# LCDTFT_CTP_FPC6P_10_1INCH_ER-TPC101-1.net
KiCad netlist of a schematic drawn in Altium Designer
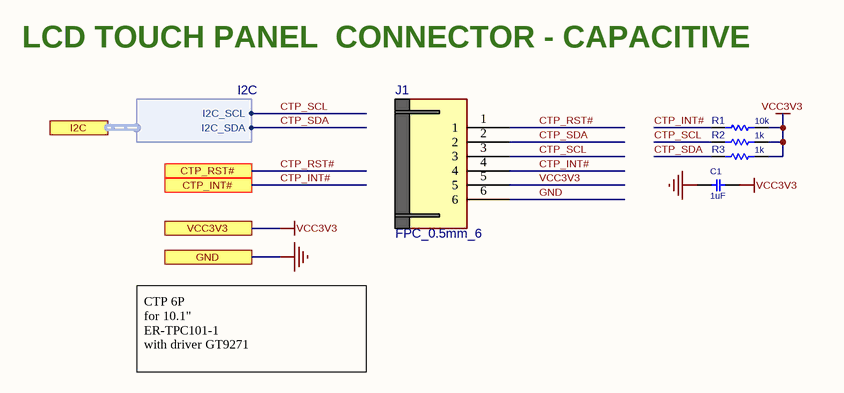
[diagram p0: LCDTFT_CTP_FPC6P_10.1INCH_ER-TPC101-1.SchDoc]

(export (version "E")
  (design (tool "Eeschema 10.0.6"))
  (components
    (comp (ref "C1")
      (value "1uF")
      (footprint "C0402")
      (description "CAP, MLCC")
      (fields (field (name "MANF_P#") "CL05A105KO5NNND") (field (name "MANF") "Samsung"))
      (libsource (lib "passive_smd") (part "CAP_SMD_MLCC"))
    )
    (comp (ref "J1")
      (value "FPC_0.5mm_6")
      (footprint "FPC50_6")
      (description "CONN, FPC, 0.50mm pitch, RightAngle, Bot. Contact, Hinge type")
      (fields (field (name "MANF") "FCI") (field (name "MANF_P#") "SFV6R1STBE1HLF"))
      (libsource (lib "conn_fpc") (part "FPC50_6"))
    )
    (comp (ref "R1")
      (value "10k")
      (footprint "R0402")
      (description "RESISTOR, SMD")
      (libsource (lib "passive_res_smd") (part "RES_SMD"))
    )
    (comp (ref "R2")
      (value "1k")
      (footprint "R0402")
      (description "RESISTOR, SMD")
      (libsource (lib "passive_res_smd") (part "RES_SMD"))
    )
    (comp (ref "R3")
      (value "1k")
      (footprint "R0402")
      (description "RESISTOR, SMD")
      (libsource (lib "passive_res_smd") (part "RES_SMD"))
    )
  )
  (nets
    (net (code "2") (name "/CTP_INT#") (class "Default")
      (node (ref "J1") (pin "4") (pinfunction "4_4") (pintype "passive"))
      (node (ref "R1") (pin "1") (pinfunction "1_1") (pintype "passive"))
    )
    (net (code "3") (name "/CTP_RST#") (class "Default")
      (node (ref "J1") (pin "1") (pinfunction "1_1") (pintype "passive"))
    )
    (net (code "4") (name "/CTP_SCL") (class "Default")
      (node (ref "J1") (pin "3") (pinfunction "3_3") (pintype "passive"))
      (node (ref "R2") (pin "1") (pinfunction "1_1") (pintype "passive"))
    )
    (net (code "5") (name "/CTP_SDA") (class "Default")
      (node (ref "J1") (pin "2") (pinfunction "2_2") (pintype "passive"))
      (node (ref "R3") (pin "1") (pinfunction "1_1") (pintype "passive"))
    )
    (net (code "7") (name "GND") (class "Default")
      (node (ref "C1") (pin "2") (pinfunction "2_2") (pintype "passive"))
      (node (ref "J1") (pin "6") (pinfunction "6_6") (pintype "passive"))
    )
    (net (code "8") (name "VCC3V3") (class "Default")
      (node (ref "C1") (pin "1") (pinfunction "1_1") (pintype "passive"))
      (node (ref "J1") (pin "5") (pinfunction "5_5") (pintype "passive"))
      (node (ref "R1") (pin "2") (pinfunction "2_2") (pintype "passive"))
      (node (ref "R2") (pin "2") (pinfunction "2_2") (pintype "passive"))
      (node (ref "R3") (pin "2") (pinfunction "2_2") (pintype "passive"))
    )
  )
)
